# Sheet1.net
KiCad netlist of a schematic drawn in Altium Designer
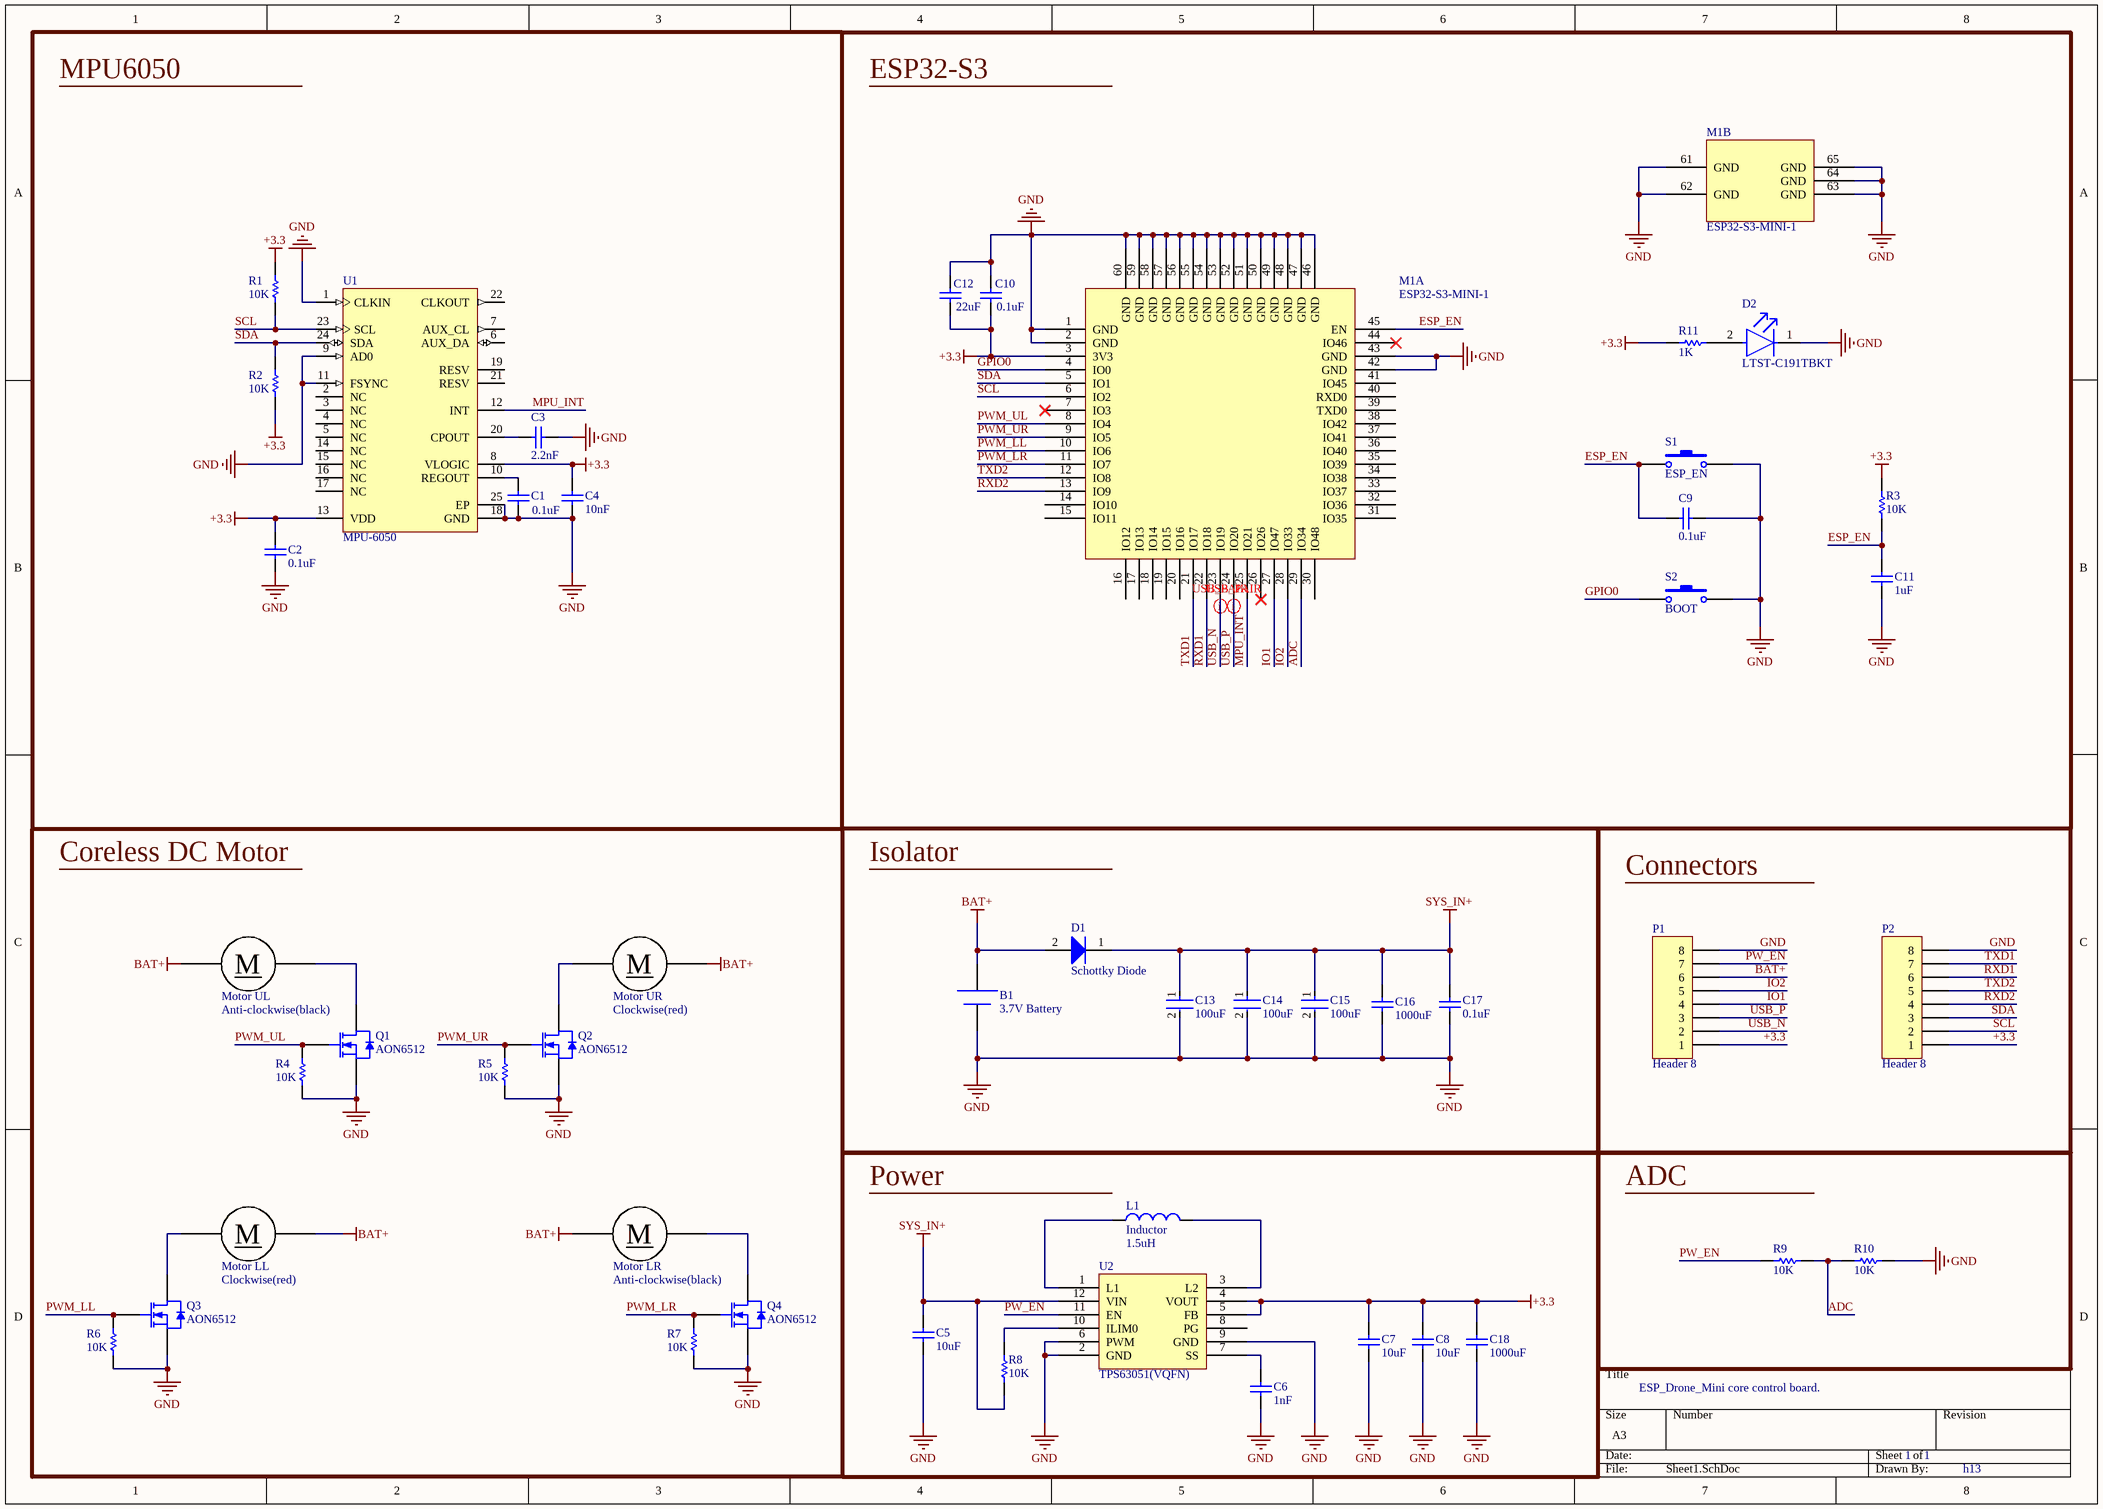
[diagram p0: Sheet1.SchDoc]

(export (version "E")
  (design (tool "Eeschema 10.0.6"))
  (components
    (comp (ref "B1")
      (value "3.7V Battery")
      (footprint "51005 SMT 2Pin")
      (description "3.7V")
      (libsource (lib "Battery") (part "Battery"))
    )
    (comp (ref "C1")
      (value "0.1uF")
      (footprint "CAPC2013X94X50LL20T25")
      (fields
        (field (name "PART NUMBER") "08051C222JAT2A")
        (field (name "MANUFACTURER") "AVX Interconnect / Elco")
      )
      (libsource (lib "Altium Content Vault") (part "CAP"))
    )
    (comp (ref "C2")
      (value "0.1uF")
      (footprint "CAPC2013X94X50LL20T25")
      (fields
        (field (name "PART NUMBER") "08051C222JAT2A")
        (field (name "MANUFACTURER") "AVX Interconnect / Elco")
      )
      (libsource (lib "Altium Content Vault") (part "CAP"))
    )
    (comp (ref "C3")
      (value "2.2nF")
      (footprint "CAPC2013X94X50LL20T25")
      (fields
        (field (name "PART NUMBER") "08051C222JAT2A")
        (field (name "MANUFACTURER") "AVX Interconnect / Elco")
      )
      (libsource (lib "Altium Content Vault") (part "CAP"))
    )
    (comp (ref "C4")
      (value "10nF")
      (footprint "CAPC2013X94X50LL20T25")
      (fields
        (field (name "PART NUMBER") "08051C222JAT2A")
        (field (name "MANUFACTURER") "AVX Interconnect / Elco")
      )
      (libsource (lib "Altium Content Vault") (part "CAP"))
    )
    (comp (ref "C5")
      (value "10uF")
      (footprint "CAPC2013X94X50LL20T25")
      (fields
        (field (name "PART NUMBER") "08051C222JAT2A")
        (field (name "MANUFACTURER") "AVX Interconnect / Elco")
      )
      (libsource (lib "Altium Content Vault") (part "CAP"))
    )
    (comp (ref "C6")
      (value "1nF")
      (footprint "CAPC2013X94X50LL20T25")
      (fields
        (field (name "PART NUMBER") "08051C222JAT2A")
        (field (name "MANUFACTURER") "AVX Interconnect / Elco")
      )
      (libsource (lib "Altium Content Vault") (part "CAP"))
    )
    (comp (ref "C7")
      (value "10uF")
      (footprint "CAPC2013X94X50LL20T25")
      (fields
        (field (name "PART NUMBER") "08051C222JAT2A")
        (field (name "MANUFACTURER") "AVX Interconnect / Elco")
      )
      (libsource (lib "Altium Content Vault") (part "CAP"))
    )
    (comp (ref "C8")
      (value "10uF")
      (footprint "CAPC2013X94X50LL20T25")
      (fields
        (field (name "PART NUMBER") "08051C222JAT2A")
        (field (name "MANUFACTURER") "AVX Interconnect / Elco")
      )
      (libsource (lib "Altium Content Vault") (part "CAP"))
    )
    (comp (ref "C9")
      (value "0.1uF")
      (footprint "CAPC2013X94X50LL20T25")
      (fields
        (field (name "PART NUMBER") "08051C222JAT2A")
        (field (name "MANUFACTURER") "AVX Interconnect / Elco")
      )
      (libsource (lib "Altium Content Vault") (part "CAP"))
    )
    (comp (ref "C10")
      (value "0.1uF")
      (footprint "CAPC2013X94X50LL20T25")
      (fields
        (field (name "PART NUMBER") "08051C222JAT2A")
        (field (name "MANUFACTURER") "AVX Interconnect / Elco")
      )
      (libsource (lib "Altium Content Vault") (part "CAP"))
    )
    (comp (ref "C11")
      (value "1uF")
      (footprint "CAPC2013X94X50LL20T25")
      (fields
        (field (name "PART NUMBER") "08051C222JAT2A")
        (field (name "MANUFACTURER") "AVX Interconnect / Elco")
      )
      (libsource (lib "Altium Content Vault") (part "CAP"))
    )
    (comp (ref "C12")
      (value "22uF")
      (footprint "CAPC2013X94X50LL20T25")
      (fields
        (field (name "PART NUMBER") "08051C222JAT2A")
        (field (name "MANUFACTURER") "AVX Interconnect / Elco")
      )
      (libsource (lib "Altium Content Vault") (part "CAP"))
    )
    (comp (ref "C13")
      (value "100uF")
      (footprint "FP-C1210C107M9PACTU-MFG")
      (description "CAP CER 100UF 6.3V X5R 1210")
      (fields (field (name "VOLTAGE") "6.3V") (field (name "TOLERANCE") "20%"))
      (libsource (lib "Altium Content Vault") (part "b4654b650e69147ec39a6b967a45e02"))
    )
    (comp (ref "C14")
      (value "100uF")
      (footprint "FP-C1210C107M9PACTU-MFG")
      (description "CAP CER 100UF 6.3V X5R 1210")
      (fields (field (name "VOLTAGE") "6.3V") (field (name "TOLERANCE") "20%"))
      (libsource (lib "Altium Content Vault") (part "b4654b650e69147ec39a6b967a45e02"))
    )
    (comp (ref "C15")
      (value "100uF")
      (footprint "FP-C1210C107M9PACTU-MFG")
      (description "CAP CER 100UF 6.3V X5R 1210")
      (fields (field (name "VOLTAGE") "6.3V") (field (name "TOLERANCE") "20%"))
      (libsource (lib "Altium Content Vault") (part "b4654b650e69147ec39a6b967a45e02"))
    )
    (comp (ref "C16")
      (value "1000uF")
      (footprint "SMD-EC8X8X10")
      (description "Capacitor")
      (fields (field (name "Comment") "Cap") (field (name "PUBLISHER") "Altium Limited"))
      (libsource (lib "Miscellaneous Devices") (part "Cap"))
    )
    (comp (ref "C17")
      (value "0.1uF")
      (footprint "CAPC2013X94X50LL20T25")
      (fields
        (field (name "PART NUMBER") "08051C222JAT2A")
        (field (name "MANUFACTURER") "AVX Interconnect / Elco")
      )
      (libsource (lib "Altium Content Vault") (part "CAP"))
    )
    (comp (ref "C18")
      (value "1000uF")
      (footprint "SMD-EC8X8X10")
      (description "Capacitor")
      (fields (field (name "Comment") "Cap") (field (name "PUBLISHER") "Altium Limited"))
      (libsource (lib "Miscellaneous Devices") (part "Cap"))
    )
    (comp (ref "D1")
      (value "Schottky Diode")
      (footprint "ONSC-SOD-123-2-425-04_V")
      (description "Schottky Barrier Diode, 2-Pin SOD-123, Pb-Free, Tape and Reel")
      (fields (field (name "PARTNUMBER") "BAT54T1G") (field (name "MANUFACTURER") "On Semiconductor"))
      (libsource (lib "Altium Content Vault") (part "ONSC-D-K1A2-2"))
    )
    (comp (ref "D2")
      (value "LTST-C191TBKT")
      (footprint "FP-LTST-C191TBKT-MFG")
      (description "LED BLUE CLEAR CHIP SMD")
      (libsource (lib "Altium Content Vault") (part "8706943c75ba83719d021d2fdc84c58"))
    )
    (comp (ref "L1")
      (value "Inductor")
      (footprint "4020")
      (fields (field (name "ALTIUM_VALUE") "1.5uH") (field (name "PUBLISHER") "Altium Limited"))
      (libsource (lib "Miscellaneous Devices") (part "Inductor"))
    )
    (comp (ref "M1")
      (value "ESP32-S3-MINI-1")
      (footprint "PCBComponent_1")
      (libsource (lib "ESP32-S3") (part "ESP32-S3-MINI-1"))
    )
    (comp (ref "Motor LL")
      (value "Motor DC")
      (footprint "HDR1X2")
      (libsource (lib "Motor") (part "Motor DC"))
    )
    (comp (ref "Motor LR")
      (value "Motor DC")
      (footprint "HDR1X2")
      (libsource (lib "Motor") (part "Motor DC"))
    )
    (comp (ref "Motor UL")
      (value "Motor DC")
      (footprint "HDR1X2")
      (libsource (lib "Motor") (part "Motor DC"))
    )
    (comp (ref "Motor UR")
      (value "Motor DC")
      (footprint "HDR1X2")
      (libsource (lib "Motor") (part "Motor DC"))
    )
    (comp (ref "P1")
      (value "Header 8")
      (footprint "HDR1X8")
      (description "Header, 8-Pin")
      (fields (field (name "PUBLISHER") "Altium Limited"))
      (libsource (lib "Miscellaneous Connectors") (part "Header 8"))
    )
    (comp (ref "P2")
      (value "Header 8")
      (footprint "HDR1X8")
      (description "Header, 8-Pin")
      (fields (field (name "PUBLISHER") "Altium Limited"))
      (libsource (lib "Miscellaneous Connectors") (part "Header 8"))
    )
    (comp (ref "Q1")
      (value "AON6512")
      (footprint "AON6512:AON6512")
      (description "N-Channel OptiMOS Power-Transistor, 60 V VDS, 100 A ID, -55 to 175 degC, PG-TO262-3-1, Tube, Green")
      (fields (field (name "MANUFACTURER") "Infineon") (field (name "PARTNUMBER") "IPI029N06N"))
      (libsource (lib "Altium Content Vault") (part "INF-NEMOS-GDS-3"))
    )
    (comp (ref "Q2")
      (value "AON6512")
      (footprint "AON6512:AON6512")
      (description "N-Channel OptiMOS Power-Transistor, 60 V VDS, 100 A ID, -55 to 175 degC, PG-TO262-3-1, Tube, Green")
      (fields (field (name "MANUFACTURER") "Infineon") (field (name "PARTNUMBER") "IPI029N06N"))
      (libsource (lib "Altium Content Vault") (part "INF-NEMOS-GDS-3"))
    )
    (comp (ref "Q3")
      (value "AON6512")
      (footprint "AON6512:AON6512")
      (description "N-Channel OptiMOS Power-Transistor, 60 V VDS, 100 A ID, -55 to 175 degC, PG-TO262-3-1, Tube, Green")
      (fields (field (name "MANUFACTURER") "Infineon") (field (name "PARTNUMBER") "IPI029N06N"))
      (libsource (lib "Altium Content Vault") (part "INF-NEMOS-GDS-3"))
    )
    (comp (ref "Q4")
      (value "AON6512")
      (footprint "AON6512:AON6512")
      (description "N-Channel OptiMOS Power-Transistor, 60 V VDS, 100 A ID, -55 to 175 degC, PG-TO262-3-1, Tube, Green")
      (fields (field (name "MANUFACTURER") "Infineon") (field (name "PARTNUMBER") "IPI029N06N"))
      (libsource (lib "Altium Content Vault") (part "INF-NEMOS-GDS-3"))
    )
    (comp (ref "R1")
      (value "10K")
      (footprint "RESC2013X60X40LL20T25_A")
      (fields (field (name "TOLERANCE") "0.1%") (field (name "MANUFACTURER") "Panasonic"))
      (libsource (lib "Altium Content Vault") (part "RES-2"))
    )
    (comp (ref "R2")
      (value "10K")
      (footprint "RESC2013X60X40LL20T25_A")
      (fields (field (name "TOLERANCE") "0.1%") (field (name "MANUFACTURER") "Panasonic"))
      (libsource (lib "Altium Content Vault") (part "RES-2"))
    )
    (comp (ref "R3")
      (value "10K")
      (footprint "RESC2013X60X40LL20T25_A")
      (fields (field (name "TOLERANCE") "0.1%") (field (name "MANUFACTURER") "Panasonic"))
      (libsource (lib "Altium Content Vault") (part "RES-2"))
    )
    (comp (ref "R4")
      (value "10K")
      (footprint "RESC2013X60X40LL20T25_A")
      (fields (field (name "TOLERANCE") "0.1%") (field (name "MANUFACTURER") "Panasonic"))
      (libsource (lib "Altium Content Vault") (part "RES-2"))
    )
    (comp (ref "R5")
      (value "10K")
      (footprint "RESC2013X60X40LL20T25_A")
      (fields (field (name "TOLERANCE") "0.1%") (field (name "MANUFACTURER") "Panasonic"))
      (libsource (lib "Altium Content Vault") (part "RES-2"))
    )
    (comp (ref "R6")
      (value "10K")
      (footprint "RESC2013X60X40LL20T25_A")
      (fields (field (name "TOLERANCE") "0.1%") (field (name "MANUFACTURER") "Panasonic"))
      (libsource (lib "Altium Content Vault") (part "RES-2"))
    )
    (comp (ref "R7")
      (value "10K")
      (footprint "RESC2013X60X40LL20T25_A")
      (fields (field (name "TOLERANCE") "0.1%") (field (name "MANUFACTURER") "Panasonic"))
      (libsource (lib "Altium Content Vault") (part "RES-2"))
    )
    (comp (ref "R8")
      (value "10K")
      (footprint "RESC2013X60X40LL20T25_A")
      (fields (field (name "TOLERANCE") "0.1%") (field (name "MANUFACTURER") "Panasonic"))
      (libsource (lib "Altium Content Vault") (part "RES-2"))
    )
    (comp (ref "R9")
      (value "10K")
      (footprint "RESC2013X60X40LL20T25_A")
      (fields (field (name "TOLERANCE") "0.1%") (field (name "MANUFACTURER") "Panasonic"))
      (libsource (lib "Altium Content Vault") (part "RES-2"))
    )
    (comp (ref "R10")
      (value "10K")
      (footprint "RESC2013X60X40LL20T25_A")
      (fields (field (name "TOLERANCE") "0.1%") (field (name "MANUFACTURER") "Panasonic"))
      (libsource (lib "Altium Content Vault") (part "RES-2"))
    )
    (comp (ref "R11")
      (value "1K")
      (footprint "RESC2013X60X40LL20T25_A")
      (fields (field (name "TOLERANCE") "0.1%") (field (name "MANUFACTURER") "Panasonic"))
      (libsource (lib "Altium Content Vault") (part "RES-2"))
    )
    (comp (ref "S1")
      (value "ESP_EN")
      (footprint "Button SMT 3.9*2.9")
      (description "Switch")
      (fields (field (name "PUBLISHER") "Altium Limited"))
      (libsource (lib "Miscellaneous Devices") (part "SW-PB"))
    )
    (comp (ref "S2")
      (value "BOOT")
      (footprint "Button SMT 3.9*2.9")
      (description "Switch")
      (fields (field (name "PUBLISHER") "Altium Limited"))
      (libsource (lib "Miscellaneous Devices") (part "SW-PB"))
    )
    (comp (ref "U1")
      (value "MPU-6050")
      (footprint "IS-QFN-24_V")
      (fields (field (name "MANUFACTURER") "InvenSense"))
      (libsource (lib "Altium Content Vault") (part "IS-MPU-6050-QFN-24"))
    )
    (comp (ref "U2")
      (value "TPS63051(VQFN)")
      (footprint "RMW0012A")
      (libsource (lib "TPS63051") (part "TPS63051(VQFN)"))
    )
  )
  (nets
    (net (code "1") (name "+3.3") (class "Default")
      (node (ref "C10") (pin "2") (pinfunction "2_2") (pintype "passive"))
      (node (ref "C12") (pin "2") (pinfunction "2_2") (pintype "passive"))
      (node (ref "C18") (pin "1") (pinfunction "1_1") (pintype "passive"))
      (node (ref "C2") (pin "1") (pinfunction "1_1") (pintype "passive"))
      (node (ref "C4") (pin "1") (pinfunction "1_1") (pintype "passive"))
      (node (ref "C7") (pin "2") (pinfunction "2_2") (pintype "passive"))
      (node (ref "C8") (pin "2") (pinfunction "2_2") (pintype "passive"))
      (node (ref "M1") (pin "3") (pinfunction "3V3_3") (pintype "passive"))
      (node (ref "P1") (pin "1") (pinfunction "1_1") (pintype "passive"))
      (node (ref "P2") (pin "1") (pinfunction "1_1") (pintype "passive"))
      (node (ref "R1") (pin "2") (pinfunction "2_2") (pintype "passive"))
      (node (ref "R11") (pin "1") (pinfunction "1_1") (pintype "passive"))
      (node (ref "R2") (pin "2") (pinfunction "2_2") (pintype "passive"))
      (node (ref "R3") (pin "1") (pinfunction "1_1") (pintype "passive"))
      (node (ref "U1") (pin "13") (pinfunction "VDD_13") (pintype "power_in"))
      (node (ref "U1") (pin "8") (pinfunction "VLOGIC_8") (pintype "power_in"))
      (node (ref "U2") (pin "4") (pinfunction "VOUT_4") (pintype "passive"))
      (node (ref "U2") (pin "5") (pinfunction "FB_5") (pintype "passive"))
    )
    (net (code "2") (name "/ADC") (class "Default")
      (node (ref "M1") (pin "29") (pinfunction "IO34_29") (pintype "passive"))
      (node (ref "R10") (pin "2") (pinfunction "2_2") (pintype "passive"))
      (node (ref "R9") (pin "1") (pinfunction "1_1") (pintype "passive"))
    )
    (net (code "3") (name "/ESP_EN") (class "Default")
      (node (ref "C11") (pin "1") (pinfunction "1_1") (pintype "passive"))
      (node (ref "C9") (pin "2") (pinfunction "2_2") (pintype "passive"))
      (node (ref "M1") (pin "45") (pinfunction "EN_45") (pintype "passive"))
      (node (ref "R3") (pin "2") (pinfunction "2_2") (pintype "passive"))
      (node (ref "S1") (pin "1") (pinfunction "1_1") (pintype "passive"))
    )
    (net (code "4") (name "/GPIO0") (class "Default")
      (node (ref "M1") (pin "4") (pinfunction "IO0_4") (pintype "passive"))
      (node (ref "S2") (pin "1") (pinfunction "1_1") (pintype "passive"))
    )
    (net (code "5") (name "/IO1") (class "Default")
      (node (ref "M1") (pin "27") (pinfunction "IO47_27") (pintype "passive"))
      (node (ref "P1") (pin "4") (pinfunction "4_4") (pintype "passive"))
    )
    (net (code "6") (name "/IO2") (class "Default")
      (node (ref "M1") (pin "28") (pinfunction "IO33_28") (pintype "passive"))
      (node (ref "P1") (pin "5") (pinfunction "5_5") (pintype "passive"))
    )
    (net (code "7") (name "/MPU_INT") (class "Default")
      (node (ref "M1") (pin "25") (pinfunction "IO21_25") (pintype "passive"))
      (node (ref "U1") (pin "12") (pinfunction "INT_12") (pintype "open_collector"))
    )
    (net (code "8") (name "/PWM_LL") (class "Default")
      (node (ref "M1") (pin "10") (pinfunction "IO6_10") (pintype "passive"))
      (node (ref "Q3") (pin "1") (pinfunction "GATE_1") (pintype "passive"))
      (node (ref "R6") (pin "2") (pinfunction "2_2") (pintype "passive"))
    )
    (net (code "9") (name "/PWM_LR") (class "Default")
      (node (ref "M1") (pin "11") (pinfunction "IO7_11") (pintype "passive"))
      (node (ref "Q4") (pin "1") (pinfunction "GATE_1") (pintype "passive"))
      (node (ref "R7") (pin "2") (pinfunction "2_2") (pintype "passive"))
    )
    (net (code "10") (name "/PWM_UL") (class "Default")
      (node (ref "M1") (pin "8") (pinfunction "IO4_8") (pintype "passive"))
      (node (ref "Q1") (pin "1") (pinfunction "GATE_1") (pintype "passive"))
      (node (ref "R4") (pin "2") (pinfunction "2_2") (pintype "passive"))
    )
    (net (code "11") (name "/PWM_UR") (class "Default")
      (node (ref "M1") (pin "9") (pinfunction "IO5_9") (pintype "passive"))
      (node (ref "Q2") (pin "1") (pinfunction "GATE_1") (pintype "passive"))
      (node (ref "R5") (pin "2") (pinfunction "2_2") (pintype "passive"))
    )
    (net (code "12") (name "/PW_EN") (class "Default")
      (node (ref "P1") (pin "7") (pinfunction "7_7") (pintype "passive"))
      (node (ref "R9") (pin "2") (pinfunction "2_2") (pintype "passive"))
      (node (ref "U2") (pin "11") (pinfunction "EN_11") (pintype "passive"))
    )
    (net (code "13") (name "/RXD1") (class "Default")
      (node (ref "M1") (pin "22") (pinfunction "IO18_22") (pintype "passive"))
      (node (ref "P2") (pin "6") (pinfunction "6_6") (pintype "passive"))
    )
    (net (code "14") (name "/RXD2") (class "Default")
      (node (ref "M1") (pin "13") (pinfunction "IO9_13") (pintype "passive"))
      (node (ref "P2") (pin "4") (pinfunction "4_4") (pintype "passive"))
    )
    (net (code "15") (name "/SCL") (class "Default")
      (node (ref "M1") (pin "6") (pinfunction "IO2_6") (pintype "passive"))
      (node (ref "P2") (pin "2") (pinfunction "2_2") (pintype "passive"))
      (node (ref "R1") (pin "1") (pinfunction "1_1") (pintype "passive"))
      (node (ref "U1") (pin "23") (pinfunction "SCL_23") (pintype "input"))
    )
    (net (code "16") (name "/SDA") (class "Default")
      (node (ref "M1") (pin "5") (pinfunction "IO1_5") (pintype "passive"))
      (node (ref "P2") (pin "3") (pinfunction "3_3") (pintype "passive"))
      (node (ref "R2") (pin "1") (pinfunction "1_1") (pintype "passive"))
      (node (ref "U1") (pin "24") (pinfunction "SDA_24") (pintype "bidirectional"))
    )
    (net (code "17") (name "/TXD1") (class "Default")
      (node (ref "M1") (pin "21") (pinfunction "IO17_21") (pintype "passive"))
      (node (ref "P2") (pin "7") (pinfunction "7_7") (pintype "passive"))
    )
    (net (code "18") (name "/TXD2") (class "Default")
      (node (ref "M1") (pin "12") (pinfunction "IO8_12") (pintype "passive"))
      (node (ref "P2") (pin "5") (pinfunction "5_5") (pintype "passive"))
    )
    (net (code "19") (name "/USB_N") (class "Default")
      (node (ref "M1") (pin "23") (pinfunction "IO19_23") (pintype "passive"))
      (node (ref "P1") (pin "2") (pinfunction "2_2") (pintype "passive"))
    )
    (net (code "20") (name "/USB_P") (class "Default")
      (node (ref "M1") (pin "24") (pinfunction "IO20_24") (pintype "passive"))
      (node (ref "P1") (pin "3") (pinfunction "3_3") (pintype "passive"))
    )
    (net (code "21") (name "BAT+") (class "Default")
      (node (ref "B1") (pin "1") (pinfunction "+_1") (pintype "passive"))
      (node (ref "D1") (pin "2") (pinfunction "A_2") (pintype "passive"))
      (node (ref "Motor LL") (pin "2") (pinfunction "2_2") (pintype "passive"))
      (node (ref "Motor LR") (pin "1") (pinfunction "1_1") (pintype "passive"))
      (node (ref "Motor UL") (pin "1") (pinfunction "1_1") (pintype "passive"))
      (node (ref "Motor UR") (pin "2") (pinfunction "2_2") (pintype "passive"))
      (node (ref "P1") (pin "6") (pinfunction "6_6") (pintype "passive"))
    )
    (net (code "22") (name "GND") (class "Default")
      (node (ref "B1") (pin "2") (pinfunction "-_2") (pintype "passive"))
      (node (ref "C1") (pin "2") (pinfunction "2_2") (pintype "passive"))
      (node (ref "C10") (pin "1") (pinfunction "1_1") (pintype "passive"))
      (node (ref "C11") (pin "2") (pinfunction "2_2") (pintype "passive"))
      (node (ref "C12") (pin "1") (pinfunction "1_1") (pintype "passive"))
      (node (ref "C13") (pin "2") (pinfunction "2_2") (pintype "passive"))
      (node (ref "C14") (pin "2") (pinfunction "2_2") (pintype "passive"))
      (node (ref "C15") (pin "2") (pinfunction "2_2") (pintype "passive"))
      (node (ref "C16") (pin "2") (pinfunction "2_2") (pintype "passive"))
      (node (ref "C17") (pin "2") (pinfunction "2_2") (pintype "passive"))
      (node (ref "C18") (pin "2") (pinfunction "2_2") (pintype "passive"))
      (node (ref "C2") (pin "2") (pinfunction "2_2") (pintype "passive"))
      (node (ref "C3") (pin "1") (pinfunction "1_1") (pintype "passive"))
      (node (ref "C4") (pin "2") (pinfunction "2_2") (pintype "passive"))
      (node (ref "C5") (pin "1") (pinfunction "1_1") (pintype "passive"))
      (node (ref "C6") (pin "1") (pinfunction "1_1") (pintype "passive"))
      (node (ref "C7") (pin "1") (pinfunction "1_1") (pintype "passive"))
      (node (ref "C8") (pin "1") (pinfunction "1_1") (pintype "passive"))
      (node (ref "C9") (pin "1") (pinfunction "1_1") (pintype "passive"))
      (node (ref "D2") (pin "1") (pinfunction "C_1") (pintype "passive"))
      (node (ref "M1") (pin "1") (pinfunction "GND_1") (pintype "passive"))
      (node (ref "M1") (pin "2") (pinfunction "GND_2") (pintype "passive"))
      (node (ref "M1") (pin "42") (pinfunction "GND_42") (pintype "passive"))
      (node (ref "M1") (pin "43") (pinfunction "GND_43") (pintype "passive"))
      (node (ref "M1") (pin "46") (pinfunction "GND_46") (pintype "passive"))
      (node (ref "M1") (pin "47") (pinfunction "GND_47") (pintype "passive"))
      (node (ref "M1") (pin "48") (pinfunction "GND_48") (pintype "passive"))
      (node (ref "M1") (pin "49") (pinfunction "GND_49") (pintype "passive"))
      (node (ref "M1") (pin "50") (pinfunction "GND_50") (pintype "passive"))
      (node (ref "M1") (pin "51") (pinfunction "GND_51") (pintype "passive"))
      (node (ref "M1") (pin "52") (pinfunction "GND_52") (pintype "passive"))
      (node (ref "M1") (pin "53") (pinfunction "GND_53") (pintype "passive"))
      (node (ref "M1") (pin "54") (pinfunction "GND_54") (pintype "passive"))
      (node (ref "M1") (pin "55") (pinfunction "GND_55") (pintype "passive"))
      (node (ref "M1") (pin "56") (pinfunction "GND_56") (pintype "passive"))
      (node (ref "M1") (pin "57") (pinfunction "GND_57") (pintype "passive"))
      (node (ref "M1") (pin "58") (pinfunction "GND_58") (pintype "passive"))
      (node (ref "M1") (pin "59") (pinfunction "GND_59") (pintype "passive"))
      (node (ref "M1") (pin "60") (pinfunction "GND_60") (pintype "passive"))
      (node (ref "M1") (pin "61") (pinfunction "GND_61") (pintype "passive"))
      (node (ref "M1") (pin "62") (pinfunction "GND_62") (pintype "passive"))
      (node (ref "M1") (pin "63") (pinfunction "GND_63") (pintype "passive"))
      (node (ref "M1") (pin "64") (pinfunction "GND_64") (pintype "passive"))
      (node (ref "M1") (pin "65") (pinfunction "GND_65") (pintype "passive"))
      (node (ref "P1") (pin "8") (pinfunction "8_8") (pintype "passive"))
      (node (ref "P2") (pin "8") (pinfunction "8_8") (pintype "passive"))
      (node (ref "Q1") (pin "3") (pinfunction "SOURCE_3") (pintype "passive"))
      (node (ref "Q2") (pin "3") (pinfunction "SOURCE_3") (pintype "passive"))
      (node (ref "Q3") (pin "3") (pinfunction "SOURCE_3") (pintype "passive"))
      (node (ref "Q4") (pin "3") (pinfunction "SOURCE_3") (pintype "passive"))
      (node (ref "R10") (pin "1") (pinfunction "1_1") (pintype "passive"))
      (node (ref "R4") (pin "1") (pinfunction "1_1") (pintype "passive"))
      (node (ref "R5") (pin "1") (pinfunction "1_1") (pintype "passive"))
      (node (ref "R6") (pin "1") (pinfunction "1_1") (pintype "passive"))
      (node (ref "R7") (pin "1") (pinfunction "1_1") (pintype "passive"))
      (node (ref "S1") (pin "2") (pinfunction "2_2") (pintype "passive"))
      (node (ref "S2") (pin "2") (pinfunction "2_2") (pintype "passive"))
      (node (ref "U1") (pin "1") (pinfunction "CLKIN_1") (pintype "input"))
      (node (ref "U1") (pin "11") (pinfunction "FSYNC_11") (pintype "input"))
      (node (ref "U1") (pin "18") (pinfunction "GND_18") (pintype "power_in"))
      (node (ref "U1") (pin "25") (pinfunction "EP_25") (pintype "power_in"))
      (node (ref "U1") (pin "9") (pinfunction "AD0_9") (pintype "input"))
      (node (ref "U2") (pin "2") (pinfunction "GND_2") (pintype "passive"))
      (node (ref "U2") (pin "6") (pinfunction "PWM_6") (pintype "passive"))
      (node (ref "U2") (pin "9") (pinfunction "GND_9") (pintype "passive"))
    )
    (net (code "23") (name "Net-(D2-A)") (class "Default")
      (node (ref "D2") (pin "2") (pinfunction "A_2") (pintype "passive"))
      (node (ref "R11") (pin "2") (pinfunction "2_2") (pintype "passive"))
    )
    (net (code "24") (name "Net-(Q1-DRAIN)") (class "Default")
      (node (ref "Motor UL") (pin "2") (pinfunction "2_2") (pintype "passive"))
      (node (ref "Q1") (pin "2") (pinfunction "DRAIN_2") (pintype "passive"))
    )
    (net (code "25") (name "Net-(Q2-DRAIN)") (class "Default")
      (node (ref "Motor UR") (pin "1") (pinfunction "1_1") (pintype "passive"))
      (node (ref "Q2") (pin "2") (pinfunction "DRAIN_2") (pintype "passive"))
    )
    (net (code "26") (name "Net-(Q3-DRAIN)") (class "Default")
      (node (ref "Motor LL") (pin "1") (pinfunction "1_1") (pintype "passive"))
      (node (ref "Q3") (pin "2") (pinfunction "DRAIN_2") (pintype "passive"))
    )
    (net (code "27") (name "Net-(Q4-DRAIN)") (class "Default")
      (node (ref "Motor LR") (pin "2") (pinfunction "2_2") (pintype "passive"))
      (node (ref "Q4") (pin "2") (pinfunction "DRAIN_2") (pintype "passive"))
    )
    (net (code "28") (name "Net-(U1-CPOUT)") (class "Default")
      (node (ref "C3") (pin "2") (pinfunction "2_2") (pintype "passive"))
      (node (ref "U1") (pin "20") (pinfunction "CPOUT_20") (pintype "passive"))
    )
    (net (code "29") (name "Net-(U1-REGOUT)") (class "Default")
      (node (ref "C1") (pin "1") (pinfunction "1_1") (pintype "passive"))
      (node (ref "U1") (pin "10") (pinfunction "REGOUT_10") (pintype "passive"))
    )
    (net (code "30") (name "Net-(U2-ILIM0)") (class "Default")
      (node (ref "R8") (pin "2") (pinfunction "2_2") (pintype "passive"))
      (node (ref "U2") (pin "10") (pinfunction "ILIM0_10") (pintype "passive"))
    )
    (net (code "31") (name "Net-(U2-L1)") (class "Default")
      (node (ref "L1") (pin "1") (pinfunction "1_1") (pintype "passive"))
      (node (ref "U2") (pin "1") (pinfunction "L1_1") (pintype "passive"))
    )
    (net (code "32") (name "Net-(U2-L2)") (class "Default")
      (node (ref "L1") (pin "2") (pinfunction "2_2") (pintype "passive"))
      (node (ref "U2") (pin "3") (pinfunction "L2_3") (pintype "passive"))
    )
    (net (code "33") (name "Net-(U2-SS)") (class "Default")
      (node (ref "C6") (pin "2") (pinfunction "2_2") (pintype "passive"))
      (node (ref "U2") (pin "7") (pinfunction "SS_7") (pintype "passive"))
    )
    (net (code "34") (name "SYS_IN+") (class "Default")
      (node (ref "C13") (pin "1") (pinfunction "1_1") (pintype "passive"))
      (node (ref "C14") (pin "1") (pinfunction "1_1") (pintype "passive"))
      (node (ref "C15") (pin "1") (pinfunction "1_1") (pintype "passive"))
      (node (ref "C16") (pin "1") (pinfunction "1_1") (pintype "passive"))
      (node (ref "C17") (pin "1") (pinfunction "1_1") (pintype "passive"))
      (node (ref "C5") (pin "2") (pinfunction "2_2") (pintype "passive"))
      (node (ref "D1") (pin "1") (pinfunction "K_1") (pintype "passive"))
      (node (ref "R8") (pin "1") (pinfunction "1_1") (pintype "passive"))
      (node (ref "U2") (pin "12") (pinfunction "VIN_12") (pintype "passive"))
    )
    (net (code "35") (name "unconnected-(M1A-IO3-Pad7)") (class "Default")
      (node (ref "M1") (pin "7") (pinfunction "IO3_7") (pintype "passive+no_connect"))
    )
    (net (code "36") (name "unconnected-(M1A-IO10-Pad14)") (class "Default")
      (node (ref "M1") (pin "14") (pinfunction "IO10_14") (pintype "passive"))
    )
    (net (code "37") (name "unconnected-(M1A-IO11-Pad15)") (class "Default")
      (node (ref "M1") (pin "15") (pinfunction "IO11_15") (pintype "passive"))
    )
    (net (code "38") (name "unconnected-(M1A-IO12-Pad16)") (class "Default")
      (node (ref "M1") (pin "16") (pinfunction "IO12_16") (pintype "passive"))
    )
    (net (code "39") (name "unconnected-(M1A-IO13-Pad17)") (class "Default")
      (node (ref "M1") (pin "17") (pinfunction "IO13_17") (pintype "passive"))
    )
    (net (code "40") (name "unconnected-(M1A-IO14-Pad18)") (class "Default")
      (node (ref "M1") (pin "18") (pinfunction "IO14_18") (pintype "passive"))
    )
    (net (code "41") (name "unconnected-(M1A-IO15-Pad19)") (class "Default")
      (node (ref "M1") (pin "19") (pinfunction "IO15_19") (pintype "passive"))
    )
    (net (code "42") (name "unconnected-(M1A-IO16-Pad20)") (class "Default")
      (node (ref "M1") (pin "20") (pinfunction "IO16_20") (pintype "passive"))
    )
    (net (code "43") (name "unconnected-(M1A-IO26-Pad26)") (class "Default")
      (node (ref "M1") (pin "26") (pinfunction "IO26_26") (pintype "passive+no_connect"))
    )
    (net (code "44") (name "unconnected-(M1A-IO35-Pad31)") (class "Default")
      (node (ref "M1") (pin "31") (pinfunction "IO35_31") (pintype "passive"))
    )
    (net (code "45") (name "unconnected-(M1A-IO36-Pad32)") (class "Default")
      (node (ref "M1") (pin "32") (pinfunction "IO36_32") (pintype "passive"))
    )
    (net (code "46") (name "unconnected-(M1A-IO37-Pad33)") (class "Default")
      (node (ref "M1") (pin "33") (pinfunction "IO37_33") (pintype "passive"))
    )
    (net (code "47") (name "unconnected-(M1A-IO38-Pad34)") (class "Default")
      (node (ref "M1") (pin "34") (pinfunction "IO38_34") (pintype "passive"))
    )
    (net (code "48") (name "unconnected-(M1A-IO39-Pad35)") (class "Default")
      (node (ref "M1") (pin "35") (pinfunction "IO39_35") (pintype "passive"))
    )
    (net (code "49") (name "unconnected-(M1A-IO40-Pad36)") (class "Default")
      (node (ref "M1") (pin "36") (pinfunction "IO40_36") (pintype "passive"))
    )
    (net (code "50") (name "unconnected-(M1A-IO41-Pad37)") (class "Default")
      (node (ref "M1") (pin "37") (pinfunction "IO41_37") (pintype "passive"))
    )
    (net (code "51") (name "unconnected-(M1A-IO42-Pad38)") (class "Default")
      (node (ref "M1") (pin "38") (pinfunction "IO42_38") (pintype "passive"))
    )
    (net (code "52") (name "unconnected-(M1A-IO45-Pad41)") (class "Default")
      (node (ref "M1") (pin "41") (pinfunction "IO45_41") (pintype "passive"))
    )
    (net (code "53") (name "unconnected-(M1A-IO46-Pad44)") (class "Default")
      (node (ref "M1") (pin "44") (pinfunction "IO46_44") (pintype "passive+no_connect"))
    )
    (net (code "54") (name "unconnected-(M1A-IO48-Pad30)") (class "Default")
      (node (ref "M1") (pin "30") (pinfunction "IO48_30") (pintype "passive"))
    )
    (net (code "55") (name "unconnected-(M1A-RXD0-Pad40)") (class "Default")
      (node (ref "M1") (pin "40") (pinfunction "RXD0_40") (pintype "passive"))
    )
    (net (code "56") (name "unconnected-(M1A-TXD0-Pad39)") (class "Default")
      (node (ref "M1") (pin "39") (pinfunction "TXD0_39") (pintype "passive"))
    )
    (net (code "57") (name "unconnected-(U1-AUX_CL-Pad7)") (class "Default")
      (node (ref "U1") (pin "7") (pinfunction "AUX_CL_7") (pintype "output"))
    )
    (net (code "58") (name "unconnected-(U1-AUX_DA-Pad6)") (class "Default")
      (node (ref "U1") (pin "6") (pinfunction "AUX_DA_6") (pintype "bidirectional"))
    )
    (net (code "59") (name "unconnected-(U1-CLKOUT-Pad22)") (class "Default")
      (node (ref "U1") (pin "22") (pinfunction "CLKOUT_22") (pintype "output"))
    )
    (net (code "60") (name "unconnected-(U1-NC-Pad2)") (class "Default")
      (node (ref "U1") (pin "2") (pinfunction "NC_2") (pintype "passive"))
    )
    (net (code "61") (name "unconnected-(U1-NC-Pad3)") (class "Default")
      (node (ref "U1") (pin "3") (pinfunction "NC_3") (pintype "passive"))
    )
    (net (code "62") (name "unconnected-(U1-NC-Pad4)") (class "Default")
      (node (ref "U1") (pin "4") (pinfunction "NC_4") (pintype "passive"))
    )
    (net (code "63") (name "unconnected-(U1-NC-Pad5)") (class "Default")
      (node (ref "U1") (pin "5") (pinfunction "NC_5") (pintype "passive"))
    )
    (net (code "64") (name "unconnected-(U1-NC-Pad14)") (class "Default")
      (node (ref "U1") (pin "14") (pinfunction "NC_14") (pintype "passive"))
    )
    (net (code "65") (name "unconnected-(U1-NC-Pad15)") (class "Default")
      (node (ref "U1") (pin "15") (pinfunction "NC_15") (pintype "passive"))
    )
    (net (code "66") (name "unconnected-(U1-NC-Pad16)") (class "Default")
      (node (ref "U1") (pin "16") (pinfunction "NC_16") (pintype "passive"))
    )
    (net (code "67") (name "unconnected-(U1-NC-Pad17)") (class "Default")
      (node (ref "U1") (pin "17") (pinfunction "NC_17") (pintype "passive"))
    )
    (net (code "68") (name "unconnected-(U1-RESV-Pad19)") (class "Default")
      (node (ref "U1") (pin "19") (pinfunction "RESV_19") (pintype "passive"))
    )
    (net (code "69") (name "unconnected-(U1-RESV-Pad21)") (class "Default")
      (node (ref "U1") (pin "21") (pinfunction "RESV_21") (pintype "passive"))
    )
    (net (code "70") (name "unconnected-(U2-PG-Pad8)") (class "Default")
      (node (ref "U2") (pin "8") (pinfunction "PG_8") (pintype "passive"))
    )
  )
)
